# LEDs.net
KiCad netlist of a schematic drawn in EAGLE
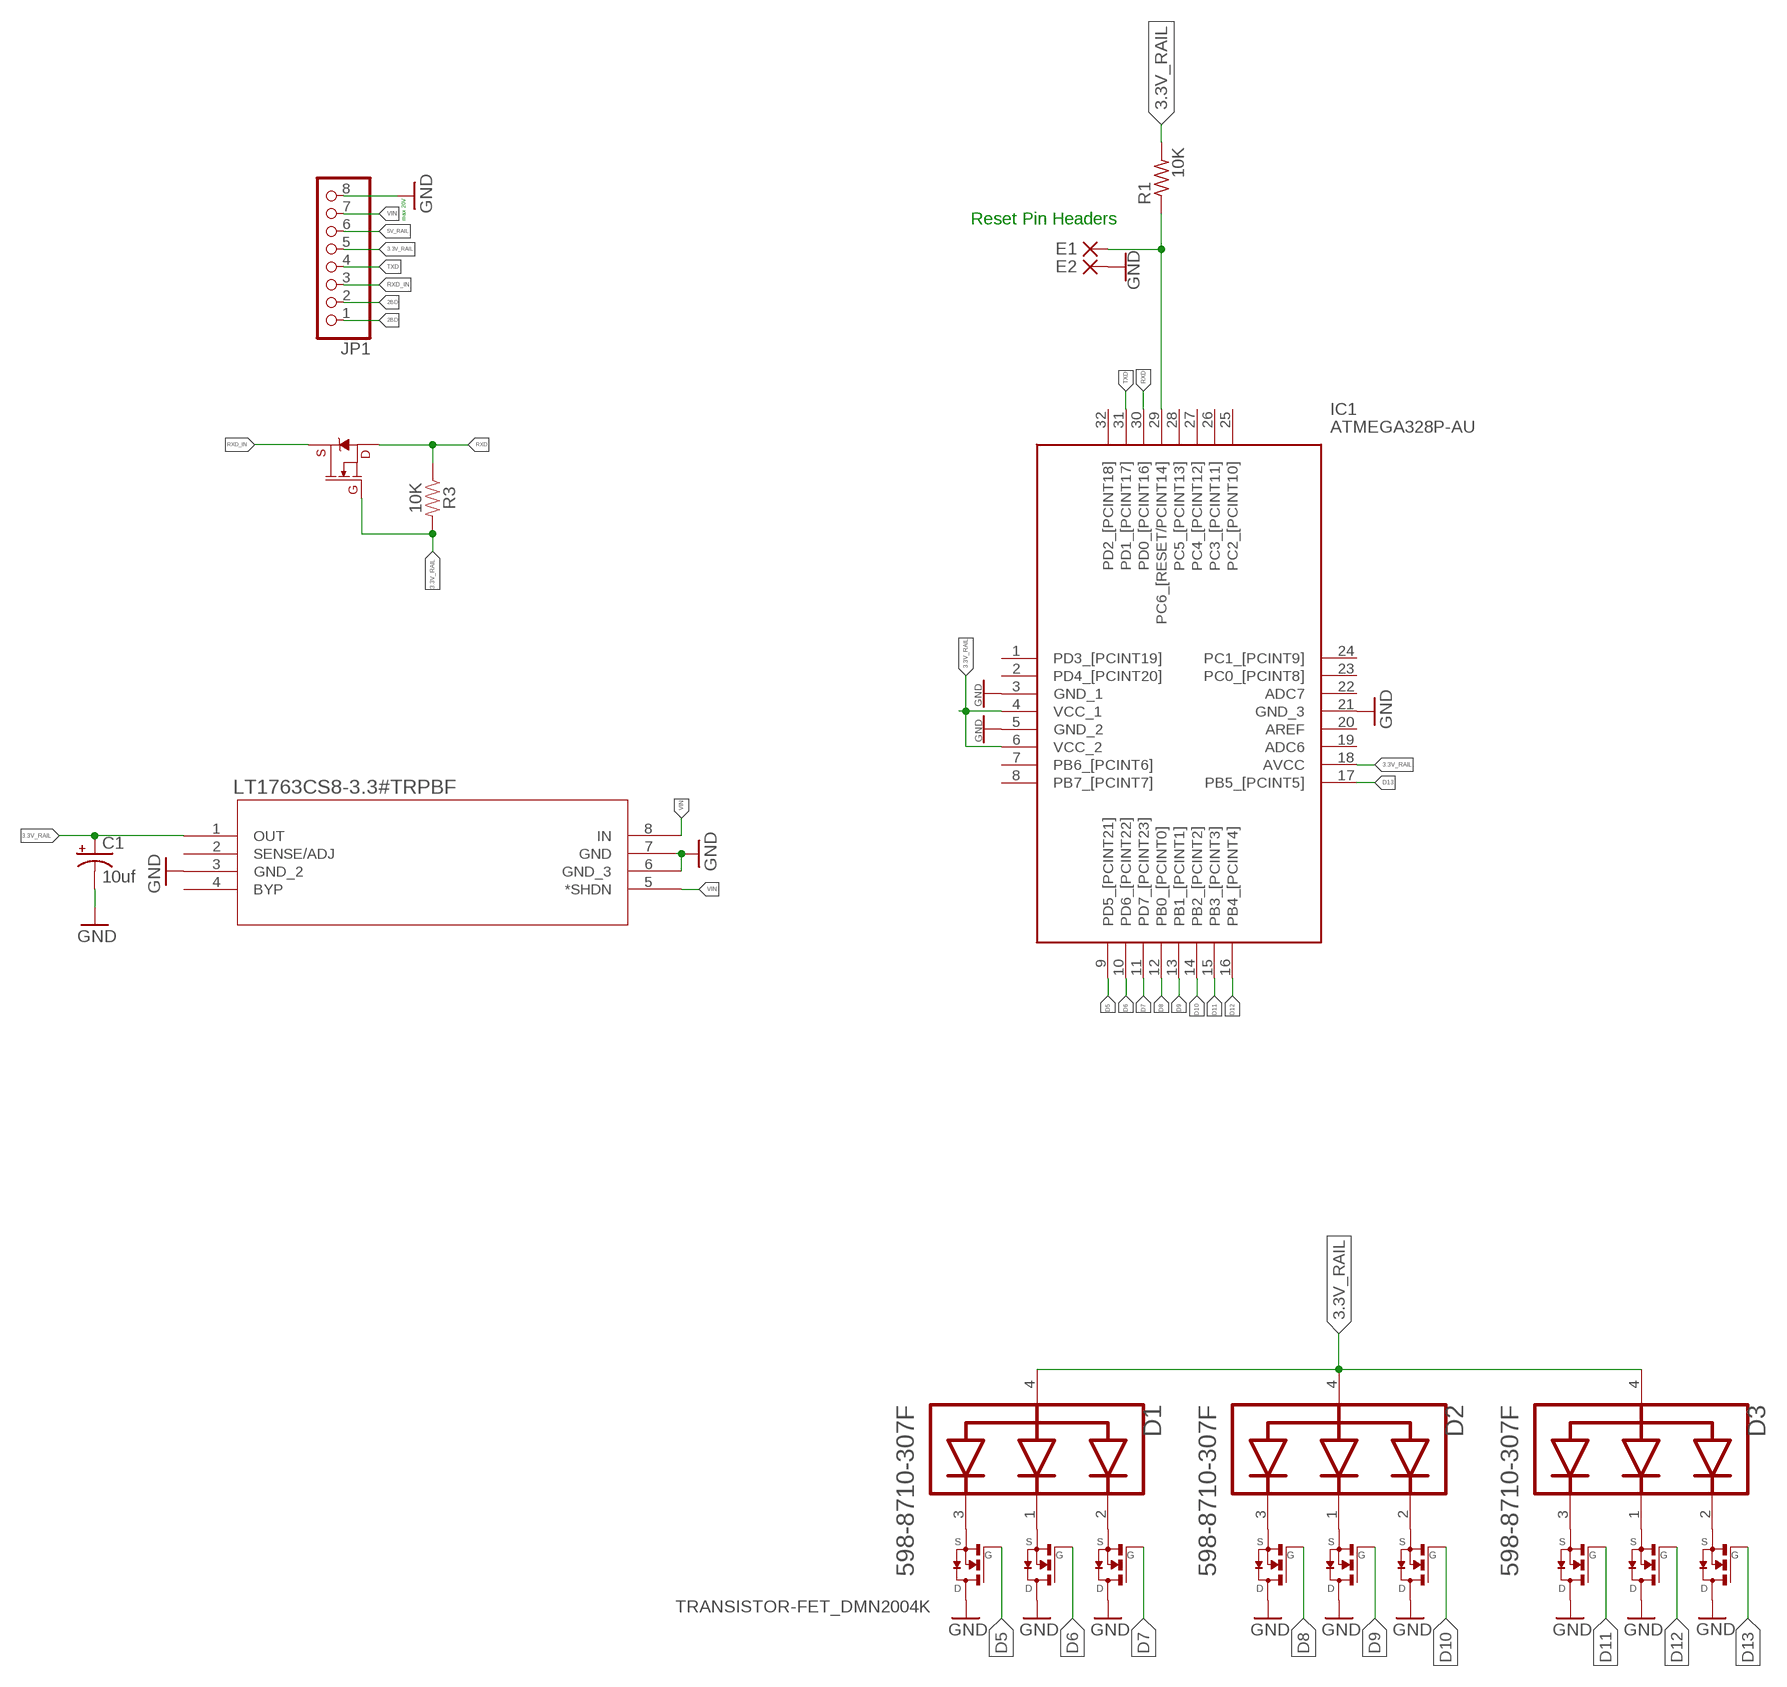
[diagram p0: schematic, sheet 1]

(export (version "E")
  (design (tool "Eeschema 10.0.6"))
  (components
    (comp (ref "C1")
      (value "10uf")
      (footprint "eagle-import:E1,8-4")
      (fields (field (name "SPICEPREFIX") "C"))
      (libsource (lib "eagle-import") (part "CPOL-USE1.8-4"))
    )
    (comp (ref "D1")
      (value "DIALIGHT_598-8710-307FDIALIGHT_598-8710-307F_0_0")
      (footprint "eagle-import:DIALIGHT_598-8710-307F_0")
      (fields
        (field (name "DIGIKEY_PART_NUMBER") "350-2096-1-ND")
        (field (name "MF") "Dialight")
        (field (name "MOUSER_PART_NUMBER") "645-598-8710-307F")
        (field (name "SPICEPREFIX") "E")
      )
      (libsource (lib "eagle-import") (part "DIALIGHT_598-8710-307FDIALIGHT_598-8710-307F_0_0"))
    )
    (comp (ref "D2")
      (value "DIALIGHT_598-8710-307FDIALIGHT_598-8710-307F_0_0")
      (footprint "eagle-import:DIALIGHT_598-8710-307F_0")
      (fields
        (field (name "DIGIKEY_PART_NUMBER") "350-2096-1-ND")
        (field (name "MF") "Dialight")
        (field (name "MOUSER_PART_NUMBER") "645-598-8710-307F")
        (field (name "SPICEPREFIX") "E")
      )
      (libsource (lib "eagle-import") (part "DIALIGHT_598-8710-307FDIALIGHT_598-8710-307F_0_0"))
    )
    (comp (ref "D3")
      (value "DIALIGHT_598-8710-307FDIALIGHT_598-8710-307F_0_0")
      (footprint "eagle-import:DIALIGHT_598-8710-307F_0")
      (fields
        (field (name "DIGIKEY_PART_NUMBER") "350-2096-1-ND")
        (field (name "MF") "Dialight")
        (field (name "MOUSER_PART_NUMBER") "645-598-8710-307F")
        (field (name "SPICEPREFIX") "E")
      )
      (libsource (lib "eagle-import") (part "DIALIGHT_598-8710-307FDIALIGHT_598-8710-307F_0_0"))
    )
    (comp (ref "E1")
      (value "DPADS_PAD-0400-S")
      (footprint "eagle-import:DPADS_0400-S")
      (libsource (lib "eagle-import") (part "DPADS_PAD-0400-S"))
    )
    (comp (ref "E2")
      (value "DPADS_PAD-0400-S")
      (footprint "eagle-import:DPADS_0400-S")
      (libsource (lib "eagle-import") (part "DPADS_PAD-0400-S"))
    )
    (comp (ref "IC1")
      (value "ATMEGA328P-AU")
      (footprint "eagle-import:QFP80P900X900X120-32N")
      (fields
        (field (name "MOUSER_PART_NUMBER") "556-ATMEGA328P-AU")
        (field (name "RS_PART_NUMBER") "1310271P")
        (field (name "SPICEPREFIX") "X")
      )
      (libsource (lib "eagle-import") (part "ATMEGA328P-AU"))
    )
    (comp (ref "JP1")
      (value "PINHD-1X8CLEANBIG")
      (footprint "eagle-import:1X08-CLEANBIG")
      (libsource (lib "eagle-import") (part "PINHD-1X8CLEANBIG"))
    )
    (comp (ref "Q1")
      (value "TRANSISTOR-FET_DMN2004K")
      (footprint "eagle-import:TRANSISTOR-FET_SOT23")
      (fields (field (name "SPICEPREFIX") "Q"))
      (libsource (lib "eagle-import") (part "TRANSISTOR-FET_DMN2004K"))
    )
    (comp (ref "Q2")
      (value "TRANSISTOR-FET_DMN2004K")
      (footprint "eagle-import:TRANSISTOR-FET_SOT23")
      (fields (field (name "SPICEPREFIX") "Q"))
      (libsource (lib "eagle-import") (part "TRANSISTOR-FET_DMN2004K"))
    )
    (comp (ref "Q3")
      (value "TRANSISTOR-FET_DMN2004K")
      (footprint "eagle-import:TRANSISTOR-FET_SOT23")
      (fields (field (name "SPICEPREFIX") "Q"))
      (libsource (lib "eagle-import") (part "TRANSISTOR-FET_DMN2004K"))
    )
    (comp (ref "Q4")
      (value "TRANSISTOR-FET_DMN2004K")
      (footprint "eagle-import:TRANSISTOR-FET_SOT23")
      (fields (field (name "SPICEPREFIX") "Q"))
      (libsource (lib "eagle-import") (part "TRANSISTOR-FET_DMN2004K"))
    )
    (comp (ref "Q5")
      (value "TRANSISTOR-FET_DMN2004K")
      (footprint "eagle-import:TRANSISTOR-FET_SOT23")
      (fields (field (name "SPICEPREFIX") "Q"))
      (libsource (lib "eagle-import") (part "TRANSISTOR-FET_DMN2004K"))
    )
    (comp (ref "Q6")
      (value "TRANSISTOR-FET_DMN2004K")
      (footprint "eagle-import:TRANSISTOR-FET_SOT23")
      (fields (field (name "SPICEPREFIX") "Q"))
      (libsource (lib "eagle-import") (part "TRANSISTOR-FET_DMN2004K"))
    )
    (comp (ref "Q7")
      (value "TRANSISTOR-FET_DMN2004K")
      (footprint "eagle-import:TRANSISTOR-FET_SOT23")
      (fields (field (name "SPICEPREFIX") "Q"))
      (libsource (lib "eagle-import") (part "TRANSISTOR-FET_DMN2004K"))
    )
    (comp (ref "Q8")
      (value "TRANSISTOR-FET_DMN2004K")
      (footprint "eagle-import:TRANSISTOR-FET_SOT23")
      (fields (field (name "SPICEPREFIX") "Q"))
      (libsource (lib "eagle-import") (part "TRANSISTOR-FET_DMN2004K"))
    )
    (comp (ref "Q9")
      (value "TRANSISTOR-FET_DMN2004K")
      (footprint "eagle-import:TRANSISTOR-FET_SOT23")
      (fields (field (name "SPICEPREFIX") "Q"))
      (libsource (lib "eagle-import") (part "TRANSISTOR-FET_DMN2004K"))
    )
    (comp (ref "Q10")
      (value "220mA/50V/3.5Ω")
      (footprint "eagle-import:SOT23-3")
      (libsource (lib "eagle-import") (part "MOSFET-NCH-BSS138"))
    )
    (comp (ref "R1")
      (value "10K")
      (footprint "eagle-import:0207_10")
      (libsource (lib "eagle-import") (part "R-US_0207/10"))
    )
    (comp (ref "R3")
      (value "10K")
      (footprint "eagle-import:AXIAL-0.3")
      (libsource (lib "eagle-import") (part "10OHM-HORIZ-1/4W-1%"))
    )
    (comp (ref "U1")
      (value "LT1763CS8-3.3#TRPBF")
      (footprint "eagle-import:SO-8_S")
      (fields
        (field (name "DIGI-KEY_PART_NUMBER") "LT1763CS8-3.3#TRPBFCT-ND")
        (field (name "MF") "Analog Devices")
        (field (name "SPICEPREFIX") "X")
      )
      (libsource (lib "eagle-import") (part "LT1763CS8-3.3#TRPBF"))
    )
  )
  (nets
    (net (code "1") (name "2BD") (class "Default")
      (node (ref "JP1") (pin "1") (pinfunction "1_1") (pintype "passive"))
      (node (ref "JP1") (pin "2") (pinfunction "2_2") (pintype "passive"))
    )
    (net (code "2") (name "3.3V_RAIL") (class "Default")
      (node (ref "C1") (pin "+") (pinfunction "+_+") (pintype "passive"))
      (node (ref "D1") (pin "4") (pinfunction "COMMON_ANODE_4") (pintype "bidirectional"))
      (node (ref "D2") (pin "4") (pinfunction "COMMON_ANODE_4") (pintype "bidirectional"))
      (node (ref "D3") (pin "4") (pinfunction "COMMON_ANODE_4") (pintype "bidirectional"))
      (node (ref "IC1") (pin "18") (pinfunction "AVCC_18") (pintype "power_in"))
      (node (ref "IC1") (pin "4") (pinfunction "VCC_1_4") (pintype "power_in"))
      (node (ref "IC1") (pin "6") (pinfunction "VCC_2_6") (pintype "power_in"))
      (node (ref "JP1") (pin "5") (pinfunction "5_5") (pintype "passive"))
      (node (ref "Q10") (pin "1") (pinfunction "G_1") (pintype "bidirectional"))
      (node (ref "R1") (pin "2") (pinfunction "2_2") (pintype "passive"))
      (node (ref "R3") (pin "P$2") (pinfunction "2_P$2") (pintype "passive"))
      (node (ref "U1") (pin "1") (pinfunction "OUT_1") (pintype "output"))
    )
    (net (code "3") (name "5V_RAIL") (class "Default")
      (node (ref "JP1") (pin "6") (pinfunction "6_6") (pintype "passive"))
    )
    (net (code "4") (name "D5") (class "Default")
      (node (ref "IC1") (pin "9") (pinfunction "PD5_[PCINT21]_9") (pintype "bidirectional"))
      (node (ref "Q1") (pin "1") (pinfunction "G_1") (pintype "passive"))
    )
    (net (code "5") (name "D6") (class "Default")
      (node (ref "IC1") (pin "10") (pinfunction "PD6_[PCINT22]_10") (pintype "bidirectional"))
      (node (ref "Q2") (pin "1") (pinfunction "G_1") (pintype "passive"))
    )
    (net (code "6") (name "D7") (class "Default")
      (node (ref "IC1") (pin "11") (pinfunction "PD7_[PCINT23]_11") (pintype "bidirectional"))
      (node (ref "Q3") (pin "1") (pinfunction "G_1") (pintype "passive"))
    )
    (net (code "7") (name "D8") (class "Default")
      (node (ref "IC1") (pin "12") (pinfunction "PB0_[PCINT0]_12") (pintype "bidirectional"))
      (node (ref "Q4") (pin "1") (pinfunction "G_1") (pintype "passive"))
    )
    (net (code "8") (name "D9") (class "Default")
      (node (ref "IC1") (pin "13") (pinfunction "PB1_[PCINT1]_13") (pintype "bidirectional"))
      (node (ref "Q5") (pin "1") (pinfunction "G_1") (pintype "passive"))
    )
    (net (code "9") (name "D10") (class "Default")
      (node (ref "IC1") (pin "14") (pinfunction "PB2_[PCINT2]_14") (pintype "bidirectional"))
      (node (ref "Q6") (pin "1") (pinfunction "G_1") (pintype "passive"))
    )
    (net (code "10") (name "D11") (class "Default")
      (node (ref "IC1") (pin "15") (pinfunction "PB3_[PCINT3]_15") (pintype "bidirectional"))
      (node (ref "Q7") (pin "1") (pinfunction "G_1") (pintype "passive"))
    )
    (net (code "11") (name "D12") (class "Default")
      (node (ref "IC1") (pin "16") (pinfunction "PB4_[PCINT4]_16") (pintype "bidirectional"))
      (node (ref "Q8") (pin "1") (pinfunction "G_1") (pintype "passive"))
    )
    (net (code "12") (name "D13") (class "Default")
      (node (ref "IC1") (pin "17") (pinfunction "PB5_[PCINT5]_17") (pintype "bidirectional"))
      (node (ref "Q9") (pin "1") (pinfunction "G_1") (pintype "passive"))
    )
    (net (code "13") (name "GND") (class "Default")
      (node (ref "C1") (pin "-") (pinfunction "-_-") (pintype "passive"))
      (node (ref "E2") (pin "PAD") (pinfunction "P_PAD") (pintype "passive"))
      (node (ref "IC1") (pin "21") (pinfunction "GND_3_21") (pintype "power_in"))
      (node (ref "IC1") (pin "3") (pinfunction "GND_1_3") (pintype "power_in"))
      (node (ref "IC1") (pin "5") (pinfunction "GND_2_5") (pintype "power_in"))
      (node (ref "JP1") (pin "8") (pinfunction "8_8") (pintype "passive"))
      (node (ref "Q1") (pin "3") (pinfunction "D_3") (pintype "passive"))
      (node (ref "Q2") (pin "3") (pinfunction "D_3") (pintype "passive"))
      (node (ref "Q3") (pin "3") (pinfunction "D_3") (pintype "passive"))
      (node (ref "Q4") (pin "3") (pinfunction "D_3") (pintype "passive"))
      (node (ref "Q5") (pin "3") (pinfunction "D_3") (pintype "passive"))
      (node (ref "Q6") (pin "3") (pinfunction "D_3") (pintype "passive"))
      (node (ref "Q7") (pin "3") (pinfunction "D_3") (pintype "passive"))
      (node (ref "Q8") (pin "3") (pinfunction "D_3") (pintype "passive"))
      (node (ref "Q9") (pin "3") (pinfunction "D_3") (pintype "passive"))
      (node (ref "U1") (pin "3") (pinfunction "GND_2_3") (pintype "power_in"))
      (node (ref "U1") (pin "6") (pinfunction "GND_3_6") (pintype "power_in"))
      (node (ref "U1") (pin "7") (pinfunction "GND_7") (pintype "power_in"))
    )
    (net (code "14") (name "Net-(D1-BLUE_CATHODE)") (class "Default")
      (node (ref "D1") (pin "3") (pinfunction "BLUE_CATHODE_3") (pintype "bidirectional"))
      (node (ref "Q1") (pin "2") (pinfunction "S_2") (pintype "passive"))
    )
    (net (code "15") (name "Net-(D1-GREEN_CATHODE)") (class "Default")
      (node (ref "D1") (pin "1") (pinfunction "GREEN_CATHODE_1") (pintype "bidirectional"))
      (node (ref "Q2") (pin "2") (pinfunction "S_2") (pintype "passive"))
    )
    (net (code "16") (name "Net-(D1-RED_CATHODE)") (class "Default")
      (node (ref "D1") (pin "2") (pinfunction "RED_CATHODE_2") (pintype "bidirectional"))
      (node (ref "Q3") (pin "2") (pinfunction "S_2") (pintype "passive"))
    )
    (net (code "17") (name "Net-(D2-BLUE_CATHODE)") (class "Default")
      (node (ref "D2") (pin "3") (pinfunction "BLUE_CATHODE_3") (pintype "bidirectional"))
      (node (ref "Q4") (pin "2") (pinfunction "S_2") (pintype "passive"))
    )
    (net (code "18") (name "Net-(D2-GREEN_CATHODE)") (class "Default")
      (node (ref "D2") (pin "1") (pinfunction "GREEN_CATHODE_1") (pintype "bidirectional"))
      (node (ref "Q5") (pin "2") (pinfunction "S_2") (pintype "passive"))
    )
    (net (code "19") (name "Net-(D2-RED_CATHODE)") (class "Default")
      (node (ref "D2") (pin "2") (pinfunction "RED_CATHODE_2") (pintype "bidirectional"))
      (node (ref "Q6") (pin "2") (pinfunction "S_2") (pintype "passive"))
    )
    (net (code "20") (name "Net-(D3-BLUE_CATHODE)") (class "Default")
      (node (ref "D3") (pin "3") (pinfunction "BLUE_CATHODE_3") (pintype "bidirectional"))
      (node (ref "Q7") (pin "2") (pinfunction "S_2") (pintype "passive"))
    )
    (net (code "21") (name "Net-(D3-GREEN_CATHODE)") (class "Default")
      (node (ref "D3") (pin "1") (pinfunction "GREEN_CATHODE_1") (pintype "bidirectional"))
      (node (ref "Q8") (pin "2") (pinfunction "S_2") (pintype "passive"))
    )
    (net (code "22") (name "Net-(D3-RED_CATHODE)") (class "Default")
      (node (ref "D3") (pin "2") (pinfunction "RED_CATHODE_2") (pintype "bidirectional"))
      (node (ref "Q9") (pin "2") (pinfunction "S_2") (pintype "passive"))
    )
    (net (code "23") (name "Net-(E1-P)") (class "Default")
      (node (ref "E1") (pin "PAD") (pinfunction "P_PAD") (pintype "passive"))
      (node (ref "IC1") (pin "29") (pinfunction "PC6_[RESET/PCINT14]_29") (pintype "bidirectional"))
      (node (ref "R1") (pin "1") (pinfunction "1_1") (pintype "passive"))
    )
    (net (code "24") (name "RXD") (class "Default")
      (node (ref "IC1") (pin "30") (pinfunction "PD0_[PCINT16]_30") (pintype "bidirectional"))
      (node (ref "Q10") (pin "2") (pinfunction "S_2") (pintype "bidirectional"))
      (node (ref "R3") (pin "P$1") (pinfunction "1_P$1") (pintype "passive"))
    )
    (net (code "25") (name "RXD_IN") (class "Default")
      (node (ref "JP1") (pin "3") (pinfunction "3_3") (pintype "passive"))
      (node (ref "Q10") (pin "3") (pinfunction "D_3") (pintype "bidirectional"))
    )
    (net (code "26") (name "TXD") (class "Default")
      (node (ref "IC1") (pin "31") (pinfunction "PD1_[PCINT17]_31") (pintype "bidirectional"))
      (node (ref "JP1") (pin "4") (pinfunction "4_4") (pintype "passive"))
    )
    (net (code "27") (name "VIN") (class "Default")
      (node (ref "JP1") (pin "7") (pinfunction "7_7") (pintype "passive"))
      (node (ref "U1") (pin "5") (pinfunction "*SHDN_5") (pintype "passive"))
      (node (ref "U1") (pin "8") (pinfunction "IN_8") (pintype "input"))
    )
    (net (code "28") (name "unconnected-(IC1-ADC6-Pad19)") (class "Default")
      (node (ref "IC1") (pin "19") (pinfunction "ADC6_19") (pintype "bidirectional"))
    )
    (net (code "29") (name "unconnected-(IC1-ADC7-Pad22)") (class "Default")
      (node (ref "IC1") (pin "22") (pinfunction "ADC7_22") (pintype "bidirectional"))
    )
    (net (code "30") (name "unconnected-(IC1-AREF-Pad20)") (class "Default")
      (node (ref "IC1") (pin "20") (pinfunction "AREF_20") (pintype "bidirectional"))
    )
    (net (code "31") (name "unconnected-(IC1-PB6_[PCINT6]-Pad7)") (class "Default")
      (node (ref "IC1") (pin "7") (pinfunction "PB6_[PCINT6]_7") (pintype "bidirectional"))
    )
    (net (code "32") (name "unconnected-(IC1-PB7_[PCINT7]-Pad8)") (class "Default")
      (node (ref "IC1") (pin "8") (pinfunction "PB7_[PCINT7]_8") (pintype "bidirectional"))
    )
    (net (code "33") (name "unconnected-(IC1-PC0_[PCINT8]-Pad23)") (class "Default")
      (node (ref "IC1") (pin "23") (pinfunction "PC0_[PCINT8]_23") (pintype "bidirectional"))
    )
    (net (code "34") (name "unconnected-(IC1-PC1_[PCINT9]-Pad24)") (class "Default")
      (node (ref "IC1") (pin "24") (pinfunction "PC1_[PCINT9]_24") (pintype "bidirectional"))
    )
    (net (code "35") (name "unconnected-(IC1-PC2_[PCINT10]-Pad25)") (class "Default")
      (node (ref "IC1") (pin "25") (pinfunction "PC2_[PCINT10]_25") (pintype "bidirectional"))
    )
    (net (code "36") (name "unconnected-(IC1-PC3_[PCINT11]-Pad26)") (class "Default")
      (node (ref "IC1") (pin "26") (pinfunction "PC3_[PCINT11]_26") (pintype "bidirectional"))
    )
    (net (code "37") (name "unconnected-(IC1-PC4_[PCINT12]-Pad27)") (class "Default")
      (node (ref "IC1") (pin "27") (pinfunction "PC4_[PCINT12]_27") (pintype "bidirectional"))
    )
    (net (code "38") (name "unconnected-(IC1-PC5_[PCINT13]-Pad28)") (class "Default")
      (node (ref "IC1") (pin "28") (pinfunction "PC5_[PCINT13]_28") (pintype "bidirectional"))
    )
    (net (code "39") (name "unconnected-(IC1-PD2_[PCINT18]-Pad32)") (class "Default")
      (node (ref "IC1") (pin "32") (pinfunction "PD2_[PCINT18]_32") (pintype "bidirectional"))
    )
    (net (code "40") (name "unconnected-(IC1-PD3_[PCINT19]-Pad1)") (class "Default")
      (node (ref "IC1") (pin "1") (pinfunction "PD3_[PCINT19]_1") (pintype "bidirectional"))
    )
    (net (code "41") (name "unconnected-(IC1-PD4_[PCINT20]-Pad2)") (class "Default")
      (node (ref "IC1") (pin "2") (pinfunction "PD4_[PCINT20]_2") (pintype "bidirectional"))
    )
    (net (code "42") (name "unconnected-(U1-BYP-Pad4)") (class "Default")
      (node (ref "U1") (pin "4") (pinfunction "BYP_4") (pintype "passive"))
    )
    (net (code "43") (name "unconnected-(U1-SENSE{slash}ADJ-Pad2)") (class "Default")
      (node (ref "U1") (pin "2") (pinfunction "SENSE/ADJ_2") (pintype "bidirectional"))
    )
  )
)
